# rapidshark_mark_7.net
KiCad netlist of a schematic drawn in EAGLE
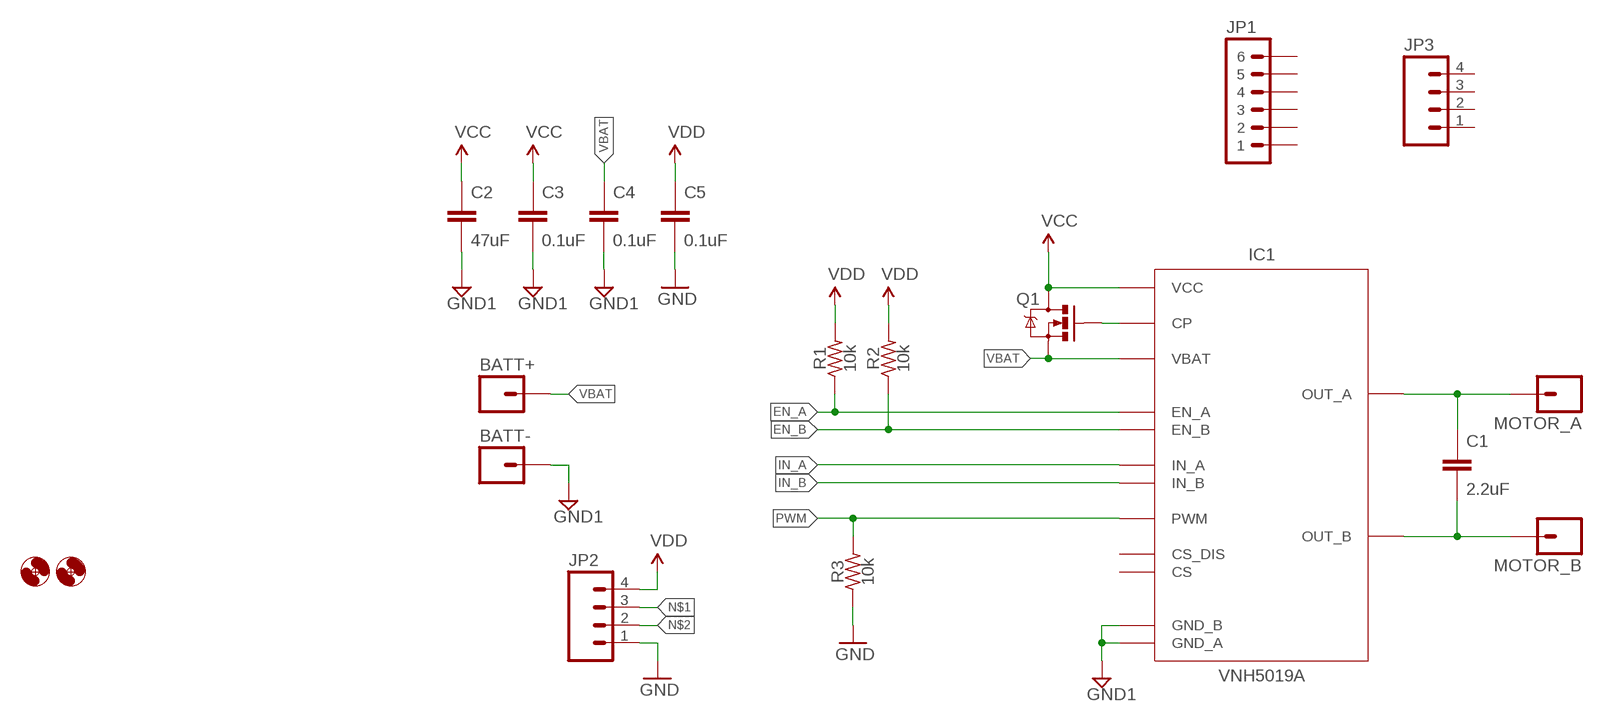
[diagram p0: schematic, sheet 1]

(export (version "E")
  (design (tool "Eeschema 10.0.6"))
  (components
    (comp (ref "BATT+")
      (value "M01PTH_2MM")
      (footprint "eagle-import:1X01_2MM")
      (libsource (lib "eagle-import") (part "M01PTH_2MM"))
    )
    (comp (ref "BATT-")
      (value "M01PTH_2MM")
      (footprint "eagle-import:1X01_2MM")
      (libsource (lib "eagle-import") (part "M01PTH_2MM"))
    )
    (comp (ref "C1")
      (value "2.2uF")
      (footprint "eagle-import:C1206")
      (libsource (lib "eagle-import") (part "CAPACITOR-CERAMICC1206"))
    )
    (comp (ref "C2")
      (value "47uF")
      (footprint "eagle-import:C3216")
      (libsource (lib "eagle-import") (part "CAPACITOR-CERAMICC3216"))
    )
    (comp (ref "C3")
      (value "0.1uF")
      (footprint "eagle-import:C0603")
      (libsource (lib "eagle-import") (part "CAPACITOR-CERAMICC0603"))
    )
    (comp (ref "C4")
      (value "0.1uF")
      (footprint "eagle-import:C0805")
      (libsource (lib "eagle-import") (part "CAPACITOR-CERAMICC0805"))
    )
    (comp (ref "C5")
      (value "0.1uF")
      (footprint "eagle-import:C0603")
      (libsource (lib "eagle-import") (part "CAPACITOR-CERAMICC0603"))
    )
    (comp (ref "H1")
      (value "HOLE#2")
      (footprint "eagle-import:HOLE-#2")
      (libsource (lib "eagle-import") (part "HOLE#2"))
    )
    (comp (ref "H2")
      (value "HOLE#2")
      (footprint "eagle-import:HOLE-#2")
      (libsource (lib "eagle-import") (part "HOLE#2"))
    )
    (comp (ref "IC1")
      (value "VNH5019A")
      (footprint "eagle-import:VNH5019A")
      (libsource (lib "eagle-import") (part "VNH5019A"))
    )
    (comp (ref "JP1")
      (value "M06JST-ZH-SMD-RA")
      (footprint "eagle-import:JST-6-ZH-RA-SMD")
      (libsource (lib "eagle-import") (part "M06JST-ZH-SMD-RA"))
    )
    (comp (ref "JP2")
      (value "M04JST-PTH")
      (footprint "eagle-import:JST-4-PH-RA-PTH")
      (libsource (lib "eagle-import") (part "M04JST-PTH"))
    )
    (comp (ref "JP3")
      (value "M04JST-SH-SMD-RA")
      (footprint "eagle-import:1X04-JST-SH-1MM-SMT-RA")
      (libsource (lib "eagle-import") (part "M04JST-SH-SMD-RA"))
    )
    (comp (ref "MOTOR_A")
      (value "M01PTH_2MM")
      (footprint "eagle-import:1X01_2MM")
      (libsource (lib "eagle-import") (part "M01PTH_2MM"))
    )
    (comp (ref "MOTOR_B")
      (value "M01PTH_2MM")
      (footprint "eagle-import:1X01_2MM")
      (libsource (lib "eagle-import") (part "M01PTH_2MM"))
    )
    (comp (ref "Q1")
      (value "PSMN4R0-30YLD")
      (footprint "eagle-import:LFPAK56")
      (libsource (lib "eagle-import") (part "MOSFET-NCHANNELPSMN4R0-30YLD"))
    )
    (comp (ref "R1")
      (value "10k")
      (footprint "eagle-import:R0603")
      (libsource (lib "eagle-import") (part "RESISTORR0603"))
    )
    (comp (ref "R2")
      (value "10k")
      (footprint "eagle-import:R0603")
      (libsource (lib "eagle-import") (part "RESISTORR0603"))
    )
    (comp (ref "R3")
      (value "10k")
      (footprint "eagle-import:R0603")
      (libsource (lib "eagle-import") (part "RESISTORR0603"))
    )
  )
  (nets
    (net (code "1") (name "EN_A") (class "Default")
      (node (ref "IC1") (pin "5") (pinfunction "EN_A_5") (pintype "bidirectional"))
      (node (ref "R1") (pin "1") (pinfunction "1_1") (pintype "passive"))
    )
    (net (code "2") (name "EN_B") (class "Default")
      (node (ref "IC1") (pin "9") (pinfunction "EN_B_9") (pintype "bidirectional"))
      (node (ref "R2") (pin "1") (pinfunction "1_1") (pintype "passive"))
    )
    (net (code "3") (name "GND") (class "Default")
      (node (ref "C5") (pin "2") (pinfunction "2_2") (pintype "passive"))
      (node (ref "JP2") (pin "1") (pinfunction "1_1") (pintype "passive"))
      (node (ref "R3") (pin "1") (pinfunction "1_1") (pintype "passive"))
    )
    (net (code "4") (name "GND1") (class "Default")
      (node (ref "BATT-") (pin "1") (pinfunction "1_1") (pintype "passive"))
      (node (ref "C2") (pin "2") (pinfunction "2_2") (pintype "passive"))
      (node (ref "C3") (pin "2") (pinfunction "2_2") (pintype "passive"))
      (node (ref "C4") (pin "2") (pinfunction "2_2") (pintype "passive"))
      (node (ref "IC1") (pin "17") (pinfunction "GND_A_17") (pintype "bidirectional"))
      (node (ref "IC1") (pin "18") (pinfunction "GND_B_18") (pintype "bidirectional"))
      (node (ref "IC1") (pin "19") (pinfunction "GND_B_19") (pintype "bidirectional"))
      (node (ref "IC1") (pin "20") (pinfunction "GND_B_20") (pintype "bidirectional"))
      (node (ref "IC1") (pin "26") (pinfunction "GND_A_26") (pintype "bidirectional"))
      (node (ref "IC1") (pin "27") (pinfunction "GND_A_27") (pintype "bidirectional"))
      (node (ref "IC1") (pin "28") (pinfunction "GND_A_28") (pintype "bidirectional"))
      (node (ref "IC1") (pin "29") (pinfunction "GND_A_29") (pintype "bidirectional"))
    )
    (net (code "5") (name "IN_A") (class "Default")
      (node (ref "IC1") (pin "4") (pinfunction "IN_A_4") (pintype "bidirectional"))
    )
    (net (code "6") (name "IN_B") (class "Default")
      (node (ref "IC1") (pin "10") (pinfunction "IN_B_10") (pintype "bidirectional"))
    )
    (net (code "7") (name "N$1") (class "Default")
      (node (ref "JP2") (pin "3") (pinfunction "3_3") (pintype "passive"))
    )
    (net (code "8") (name "N$2") (class "Default")
      (node (ref "JP2") (pin "2") (pinfunction "2_2") (pintype "passive"))
    )
    (net (code "9") (name "Net-(C1-Pad1)") (class "Default")
      (node (ref "C1") (pin "1") (pinfunction "1_1") (pintype "passive"))
      (node (ref "IC1") (pin "1") (pinfunction "OUT_A_1") (pintype "bidirectional"))
      (node (ref "IC1") (pin "24") (pinfunction "OUT_A_24") (pintype "bidirectional"))
      (node (ref "IC1") (pin "25") (pinfunction "OUT_A_25") (pintype "bidirectional"))
      (node (ref "IC1") (pin "30") (pinfunction "OUT_A_30") (pintype "bidirectional"))
      (node (ref "IC1") (pin "HS2") (pinfunction "OUT_A_HS2") (pintype "bidirectional"))
      (node (ref "MOTOR_A") (pin "1") (pinfunction "1_1") (pintype "passive"))
    )
    (net (code "10") (name "Net-(C1-Pad2)") (class "Default")
      (node (ref "C1") (pin "2") (pinfunction "2_2") (pintype "passive"))
      (node (ref "IC1") (pin "15") (pinfunction "OUT_B_15") (pintype "bidirectional"))
      (node (ref "IC1") (pin "16") (pinfunction "OUT_B_16") (pintype "bidirectional"))
      (node (ref "IC1") (pin "21") (pinfunction "OUT_B_21") (pintype "bidirectional"))
      (node (ref "IC1") (pin "22") (pinfunction "OUT_B_22") (pintype "bidirectional"))
      (node (ref "IC1") (pin "HS3") (pinfunction "OUT_B_HS3") (pintype "bidirectional"))
      (node (ref "MOTOR_B") (pin "1") (pinfunction "1_1") (pintype "passive"))
    )
    (net (code "11") (name "Net-(IC1-CP)") (class "Default")
      (node (ref "IC1") (pin "11") (pinfunction "CP_11") (pintype "bidirectional"))
      (node (ref "Q1") (pin "4") (pinfunction "G_4") (pintype "passive"))
    )
    (net (code "12") (name "PWM") (class "Default")
      (node (ref "IC1") (pin "7") (pinfunction "PWM_7") (pintype "bidirectional"))
      (node (ref "R3") (pin "2") (pinfunction "2_2") (pintype "passive"))
    )
    (net (code "13") (name "VBAT") (class "Default")
      (node (ref "BATT+") (pin "1") (pinfunction "1_1") (pintype "passive"))
      (node (ref "C4") (pin "1") (pinfunction "1_1") (pintype "passive"))
      (node (ref "IC1") (pin "12") (pinfunction "VBAT_12") (pintype "bidirectional"))
      (node (ref "Q1") (pin "1") (pinfunction "S_1") (pintype "passive"))
      (node (ref "Q1") (pin "2") (pinfunction "S_2") (pintype "passive"))
      (node (ref "Q1") (pin "3") (pinfunction "S_3") (pintype "passive"))
    )
    (net (code "14") (name "VCC") (class "Default")
      (node (ref "C2") (pin "1") (pinfunction "1_1") (pintype "passive"))
      (node (ref "C3") (pin "1") (pinfunction "1_1") (pintype "passive"))
      (node (ref "IC1") (pin "13") (pinfunction "VCC_13") (pintype "bidirectional"))
      (node (ref "IC1") (pin "14") (pinfunction "VCC_14") (pintype "bidirectional"))
      (node (ref "IC1") (pin "2") (pinfunction "VCC_2") (pintype "bidirectional"))
      (node (ref "IC1") (pin "23") (pinfunction "VCC_23") (pintype "bidirectional"))
      (node (ref "IC1") (pin "3") (pinfunction "VCC_3") (pintype "bidirectional"))
      (node (ref "IC1") (pin "HS1") (pinfunction "VCC_HS1") (pintype "bidirectional"))
      (node (ref "Q1") (pin "MB@1") (pinfunction "D_MB@1") (pintype "passive"))
      (node (ref "Q1") (pin "MB@2") (pinfunction "D_MB@2") (pintype "passive"))
    )
    (net (code "15") (name "VDD") (class "Default")
      (node (ref "C5") (pin "1") (pinfunction "1_1") (pintype "passive"))
      (node (ref "JP2") (pin "4") (pinfunction "4_4") (pintype "passive"))
      (node (ref "R1") (pin "2") (pinfunction "2_2") (pintype "passive"))
      (node (ref "R2") (pin "2") (pinfunction "2_2") (pintype "passive"))
    )
    (net (code "16") (name "unconnected-(IC1-CS-Pad8)") (class "Default")
      (node (ref "IC1") (pin "8") (pinfunction "CS_8") (pintype "bidirectional"))
    )
    (net (code "17") (name "unconnected-(IC1-CS_DIS-Pad6)") (class "Default")
      (node (ref "IC1") (pin "6") (pinfunction "CS_DIS_6") (pintype "bidirectional"))
    )
    (net (code "18") (name "unconnected-(JP1-Pad1)") (class "Default")
      (node (ref "JP1") (pin "1") (pinfunction "1_1") (pintype "passive"))
    )
    (net (code "19") (name "unconnected-(JP1-Pad2)") (class "Default")
      (node (ref "JP1") (pin "2") (pinfunction "2_2") (pintype "passive"))
    )
    (net (code "20") (name "unconnected-(JP1-Pad3)") (class "Default")
      (node (ref "JP1") (pin "3") (pinfunction "3_3") (pintype "passive"))
    )
    (net (code "21") (name "unconnected-(JP1-Pad4)") (class "Default")
      (node (ref "JP1") (pin "4") (pinfunction "4_4") (pintype "passive"))
    )
    (net (code "22") (name "unconnected-(JP1-Pad5)") (class "Default")
      (node (ref "JP1") (pin "5") (pinfunction "5_5") (pintype "passive"))
    )
    (net (code "23") (name "unconnected-(JP1-Pad6)") (class "Default")
      (node (ref "JP1") (pin "6") (pinfunction "6_6") (pintype "passive"))
    )
    (net (code "24") (name "unconnected-(JP3-Pad1)") (class "Default")
      (node (ref "JP3") (pin "1") (pinfunction "1_1") (pintype "passive"))
    )
    (net (code "25") (name "unconnected-(JP3-Pad2)") (class "Default")
      (node (ref "JP3") (pin "2") (pinfunction "2_2") (pintype "passive"))
    )
    (net (code "26") (name "unconnected-(JP3-Pad3)") (class "Default")
      (node (ref "JP3") (pin "3") (pinfunction "3_3") (pintype "passive"))
    )
    (net (code "27") (name "unconnected-(JP3-Pad4)") (class "Default")
      (node (ref "JP3") (pin "4") (pinfunction "4_4") (pintype "passive"))
    )
  )
)
